# robot.net
KiCad netlist of a schematic drawn in EAGLE
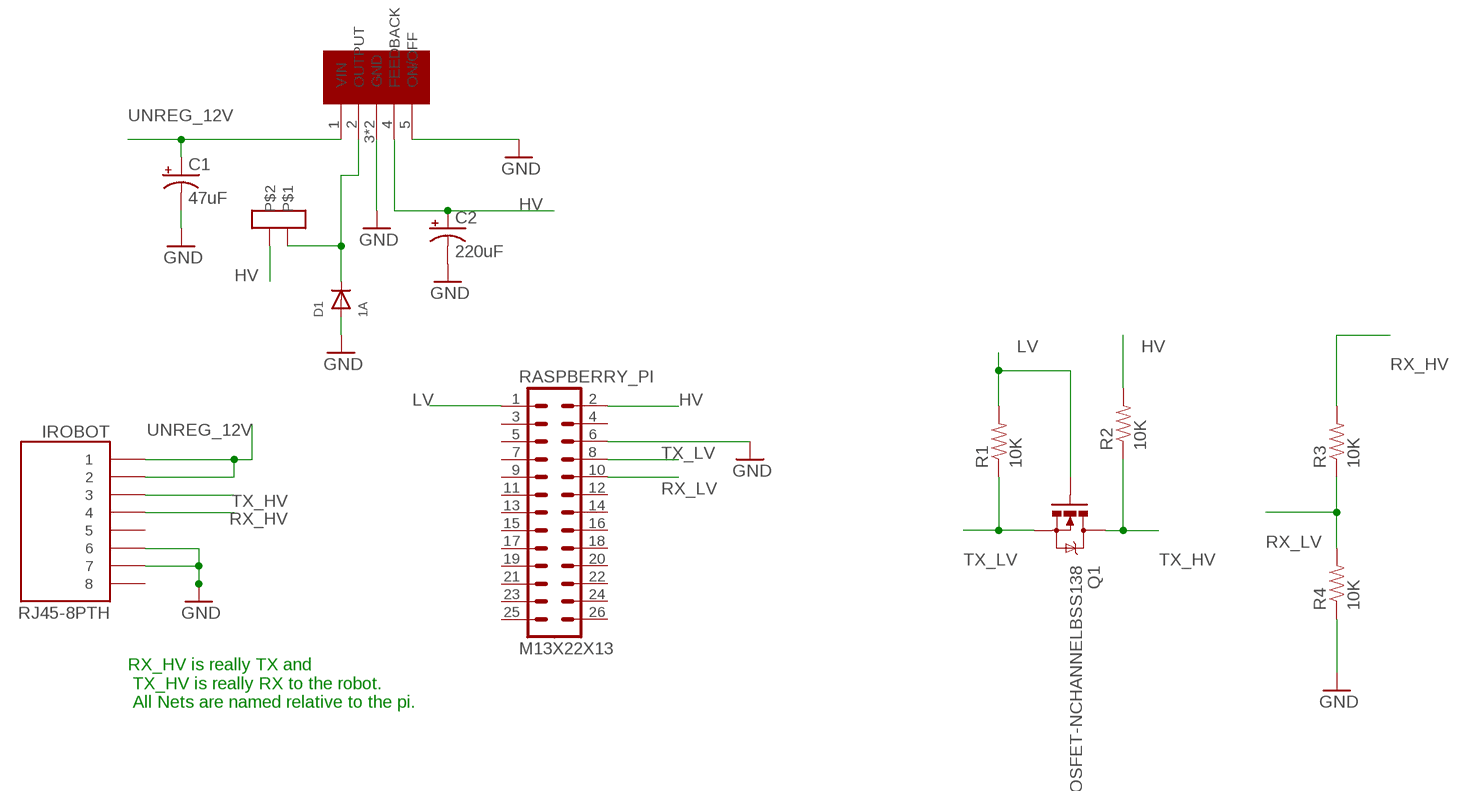
[diagram p0: schematic, sheet 1]

(export (version "E")
  (design (tool "Eeschema 10.0.6"))
  (components
    (comp (ref "C1")
      (value "47uF")
      (footprint "eagle-import:PANASONIC_D")
      (libsource (lib "eagle-import") (part "CAP_POLD"))
    )
    (comp (ref "C2")
      (value "220uF")
      (footprint "eagle-import:PANASONIC_D")
      (libsource (lib "eagle-import") (part "SparkFun-Passives_CAP_POLD"))
    )
    (comp (ref "D1")
      (value "1A")
      (footprint "eagle-import:SOD-123")
      (libsource (lib "eagle-import") (part "DIODESOD-123"))
    )
    (comp (ref "IROBOT")
      (value "RJ45-8PTH")
      (footprint "eagle-import:RJ45-8")
      (libsource (lib "eagle-import") (part "RJ45-8PTH"))
    )
    (comp (ref "Q1")
      (value "MOSFET-NCHANNELBSS138")
      (footprint "eagle-import:SOT23")
      (libsource (lib "eagle-import") (part "MOSFET-NCHANNELBSS138"))
    )
    (comp (ref "R1")
      (value "10K")
      (footprint "eagle-import:0805")
      (libsource (lib "eagle-import") (part "RESISTOR0805-RES"))
    )
    (comp (ref "R2")
      (value "10K")
      (footprint "eagle-import:0805")
      (libsource (lib "eagle-import") (part "RESISTOR0805-RES"))
    )
    (comp (ref "R3")
      (value "10K")
      (footprint "eagle-import:0805")
      (libsource (lib "eagle-import") (part "RESISTOR0805-RES"))
    )
    (comp (ref "R4")
      (value "10K")
      (footprint "eagle-import:0805")
      (libsource (lib "eagle-import") (part "RESISTOR0805-RES"))
    )
    (comp (ref "RASPBERRY_PI")
      (value "M13X22X13")
      (footprint "eagle-import:2X13")
      (libsource (lib "eagle-import") (part "M13X22X13"))
    )
    (comp (ref "U$1")
      (value "TL2575")
      (footprint "eagle-import:TO-263")
      (libsource (lib "eagle-import") (part "TL2575"))
    )
    (comp (ref "U$2")
      (value "PE-52627NL")
      (footprint "eagle-import:PE-52627NL")
      (libsource (lib "eagle-import") (part "PE-52627NL"))
    )
  )
  (nets
    (net (code "1") (name "/HV") (class "Default")
      (node (ref "C2") (pin "+") (pinfunction "+_+") (pintype "passive"))
      (node (ref "R2") (pin "2") (pinfunction "2_2") (pintype "passive"))
      (node (ref "RASPBERRY_PI") (pin "2") (pinfunction "2_2") (pintype "passive"))
      (node (ref "U$1") (pin "4") (pinfunction "FEEDBACK_4") (pintype "bidirectional"))
      (node (ref "U$2") (pin "P$2") (pinfunction "P$2_P$2") (pintype "bidirectional"))
    )
    (net (code "2") (name "/LV") (class "Default")
      (node (ref "Q1") (pin "1") (pinfunction "G_1") (pintype "passive"))
      (node (ref "R1") (pin "2") (pinfunction "2_2") (pintype "passive"))
      (node (ref "RASPBERRY_PI") (pin "1") (pinfunction "1_1") (pintype "passive"))
    )
    (net (code "3") (name "/RX_HV") (class "Default")
      (node (ref "IROBOT") (pin "4") (pinfunction "4_4") (pintype "bidirectional"))
      (node (ref "R3") (pin "2") (pinfunction "2_2") (pintype "passive"))
    )
    (net (code "4") (name "/RX_LV") (class "Default")
      (node (ref "R3") (pin "1") (pinfunction "1_1") (pintype "passive"))
      (node (ref "R4") (pin "2") (pinfunction "2_2") (pintype "passive"))
      (node (ref "RASPBERRY_PI") (pin "10") (pinfunction "10_10") (pintype "passive"))
    )
    (net (code "5") (name "/TX_HV") (class "Default")
      (node (ref "IROBOT") (pin "3") (pinfunction "3_3") (pintype "bidirectional"))
      (node (ref "Q1") (pin "3") (pinfunction "D_3") (pintype "passive"))
      (node (ref "R2") (pin "1") (pinfunction "1_1") (pintype "passive"))
    )
    (net (code "6") (name "/TX_LV") (class "Default")
      (node (ref "Q1") (pin "2") (pinfunction "S_2") (pintype "passive"))
      (node (ref "R1") (pin "1") (pinfunction "1_1") (pintype "passive"))
      (node (ref "RASPBERRY_PI") (pin "8") (pinfunction "8_8") (pintype "passive"))
    )
    (net (code "7") (name "/UNREG_12V") (class "Default")
      (node (ref "C1") (pin "+") (pinfunction "+_+") (pintype "passive"))
      (node (ref "IROBOT") (pin "1") (pinfunction "1_1") (pintype "bidirectional"))
      (node (ref "IROBOT") (pin "2") (pinfunction "2_2") (pintype "bidirectional"))
      (node (ref "U$1") (pin "1") (pinfunction "VIN_1") (pintype "bidirectional"))
    )
    (net (code "8") (name "GND") (class "Default")
      (node (ref "C1") (pin "-") (pinfunction "-_-") (pintype "passive"))
      (node (ref "C2") (pin "-") (pinfunction "-_-") (pintype "passive"))
      (node (ref "D1") (pin "A") (pinfunction "A_A") (pintype "passive"))
      (node (ref "IROBOT") (pin "6") (pinfunction "6_6") (pintype "bidirectional"))
      (node (ref "IROBOT") (pin "7") (pinfunction "7_7") (pintype "bidirectional"))
      (node (ref "R4") (pin "1") (pinfunction "1_1") (pintype "passive"))
      (node (ref "RASPBERRY_PI") (pin "6") (pinfunction "6_6") (pintype "passive"))
      (node (ref "U$1") (pin "3") (pinfunction "GND_3") (pintype "bidirectional"))
      (node (ref "U$1") (pin "5") (pinfunction "ON/OFF_5") (pintype "bidirectional"))
      (node (ref "U$1") (pin "6") (pinfunction "GND_6") (pintype "bidirectional"))
    )
    (net (code "9") (name "Net-(U$1-OUTPUT)") (class "Default")
      (node (ref "D1") (pin "C") (pinfunction "C_C") (pintype "passive"))
      (node (ref "U$1") (pin "2") (pinfunction "OUTPUT_2") (pintype "bidirectional"))
      (node (ref "U$2") (pin "P$1") (pinfunction "P$1_P$1") (pintype "bidirectional"))
    )
    (net (code "10") (name "unconnected-(IROBOT-Pad5)") (class "Default")
      (node (ref "IROBOT") (pin "5") (pinfunction "5_5") (pintype "bidirectional"))
    )
    (net (code "11") (name "unconnected-(IROBOT-Pad8)") (class "Default")
      (node (ref "IROBOT") (pin "8") (pinfunction "8_8") (pintype "bidirectional"))
    )
    (net (code "12") (name "unconnected-(RASPBERRY_PI-Pad3)") (class "Default")
      (node (ref "RASPBERRY_PI") (pin "3") (pinfunction "3_3") (pintype "passive"))
    )
    (net (code "13") (name "unconnected-(RASPBERRY_PI-Pad4)") (class "Default")
      (node (ref "RASPBERRY_PI") (pin "4") (pinfunction "4_4") (pintype "passive"))
    )
    (net (code "14") (name "unconnected-(RASPBERRY_PI-Pad5)") (class "Default")
      (node (ref "RASPBERRY_PI") (pin "5") (pinfunction "5_5") (pintype "passive"))
    )
    (net (code "15") (name "unconnected-(RASPBERRY_PI-Pad7)") (class "Default")
      (node (ref "RASPBERRY_PI") (pin "7") (pinfunction "7_7") (pintype "passive"))
    )
    (net (code "16") (name "unconnected-(RASPBERRY_PI-Pad9)") (class "Default")
      (node (ref "RASPBERRY_PI") (pin "9") (pinfunction "9_9") (pintype "passive"))
    )
    (net (code "17") (name "unconnected-(RASPBERRY_PI-Pad11)") (class "Default")
      (node (ref "RASPBERRY_PI") (pin "11") (pinfunction "11_11") (pintype "passive"))
    )
    (net (code "18") (name "unconnected-(RASPBERRY_PI-Pad12)") (class "Default")
      (node (ref "RASPBERRY_PI") (pin "12") (pinfunction "12_12") (pintype "passive"))
    )
    (net (code "19") (name "unconnected-(RASPBERRY_PI-Pad13)") (class "Default")
      (node (ref "RASPBERRY_PI") (pin "13") (pinfunction "13_13") (pintype "passive"))
    )
    (net (code "20") (name "unconnected-(RASPBERRY_PI-Pad14)") (class "Default")
      (node (ref "RASPBERRY_PI") (pin "14") (pinfunction "14_14") (pintype "passive"))
    )
    (net (code "21") (name "unconnected-(RASPBERRY_PI-Pad15)") (class "Default")
      (node (ref "RASPBERRY_PI") (pin "15") (pinfunction "15_15") (pintype "passive"))
    )
    (net (code "22") (name "unconnected-(RASPBERRY_PI-Pad16)") (class "Default")
      (node (ref "RASPBERRY_PI") (pin "16") (pinfunction "16_16") (pintype "passive"))
    )
    (net (code "23") (name "unconnected-(RASPBERRY_PI-Pad17)") (class "Default")
      (node (ref "RASPBERRY_PI") (pin "17") (pinfunction "17_17") (pintype "passive"))
    )
    (net (code "24") (name "unconnected-(RASPBERRY_PI-Pad18)") (class "Default")
      (node (ref "RASPBERRY_PI") (pin "18") (pinfunction "18_18") (pintype "passive"))
    )
    (net (code "25") (name "unconnected-(RASPBERRY_PI-Pad19)") (class "Default")
      (node (ref "RASPBERRY_PI") (pin "19") (pinfunction "19_19") (pintype "passive"))
    )
    (net (code "26") (name "unconnected-(RASPBERRY_PI-Pad20)") (class "Default")
      (node (ref "RASPBERRY_PI") (pin "20") (pinfunction "20_20") (pintype "passive"))
    )
    (net (code "27") (name "unconnected-(RASPBERRY_PI-Pad21)") (class "Default")
      (node (ref "RASPBERRY_PI") (pin "21") (pinfunction "21_21") (pintype "passive"))
    )
    (net (code "28") (name "unconnected-(RASPBERRY_PI-Pad22)") (class "Default")
      (node (ref "RASPBERRY_PI") (pin "22") (pinfunction "22_22") (pintype "passive"))
    )
    (net (code "29") (name "unconnected-(RASPBERRY_PI-Pad23)") (class "Default")
      (node (ref "RASPBERRY_PI") (pin "23") (pinfunction "23_23") (pintype "passive"))
    )
    (net (code "30") (name "unconnected-(RASPBERRY_PI-Pad24)") (class "Default")
      (node (ref "RASPBERRY_PI") (pin "24") (pinfunction "24_24") (pintype "passive"))
    )
    (net (code "31") (name "unconnected-(RASPBERRY_PI-Pad25)") (class "Default")
      (node (ref "RASPBERRY_PI") (pin "25") (pinfunction "25_25") (pintype "passive"))
    )
    (net (code "32") (name "unconnected-(RASPBERRY_PI-Pad26)") (class "Default")
      (node (ref "RASPBERRY_PI") (pin "26") (pinfunction "26_26") (pintype "passive"))
    )
  )
)
